# spielekonsole_schaltplan_03_05.net
KiCad netlist of a schematic drawn in EAGLE
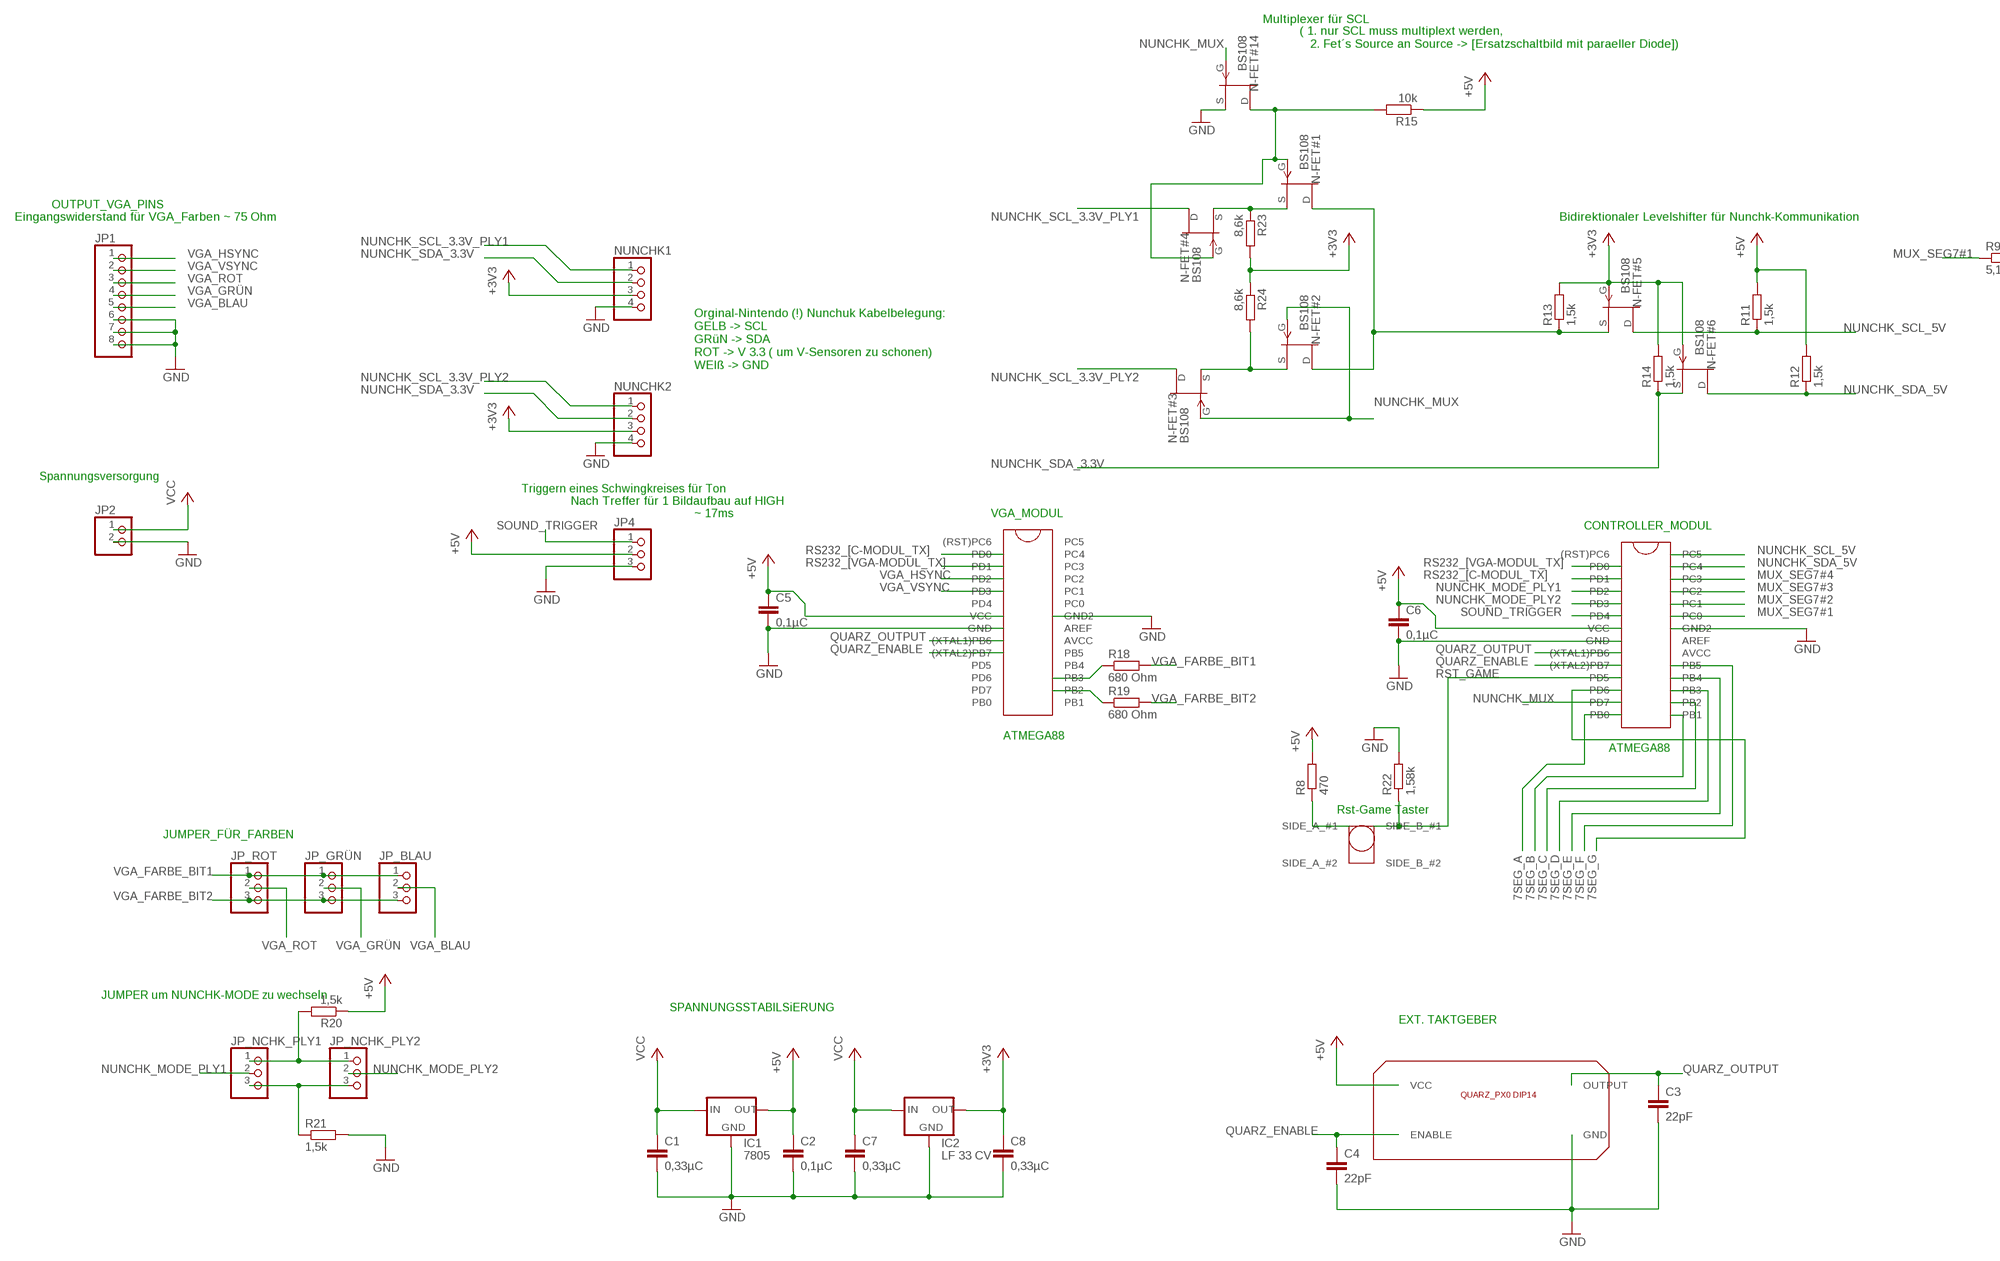
[diagram p0: schematic, sheet 1, part 1 of 2]
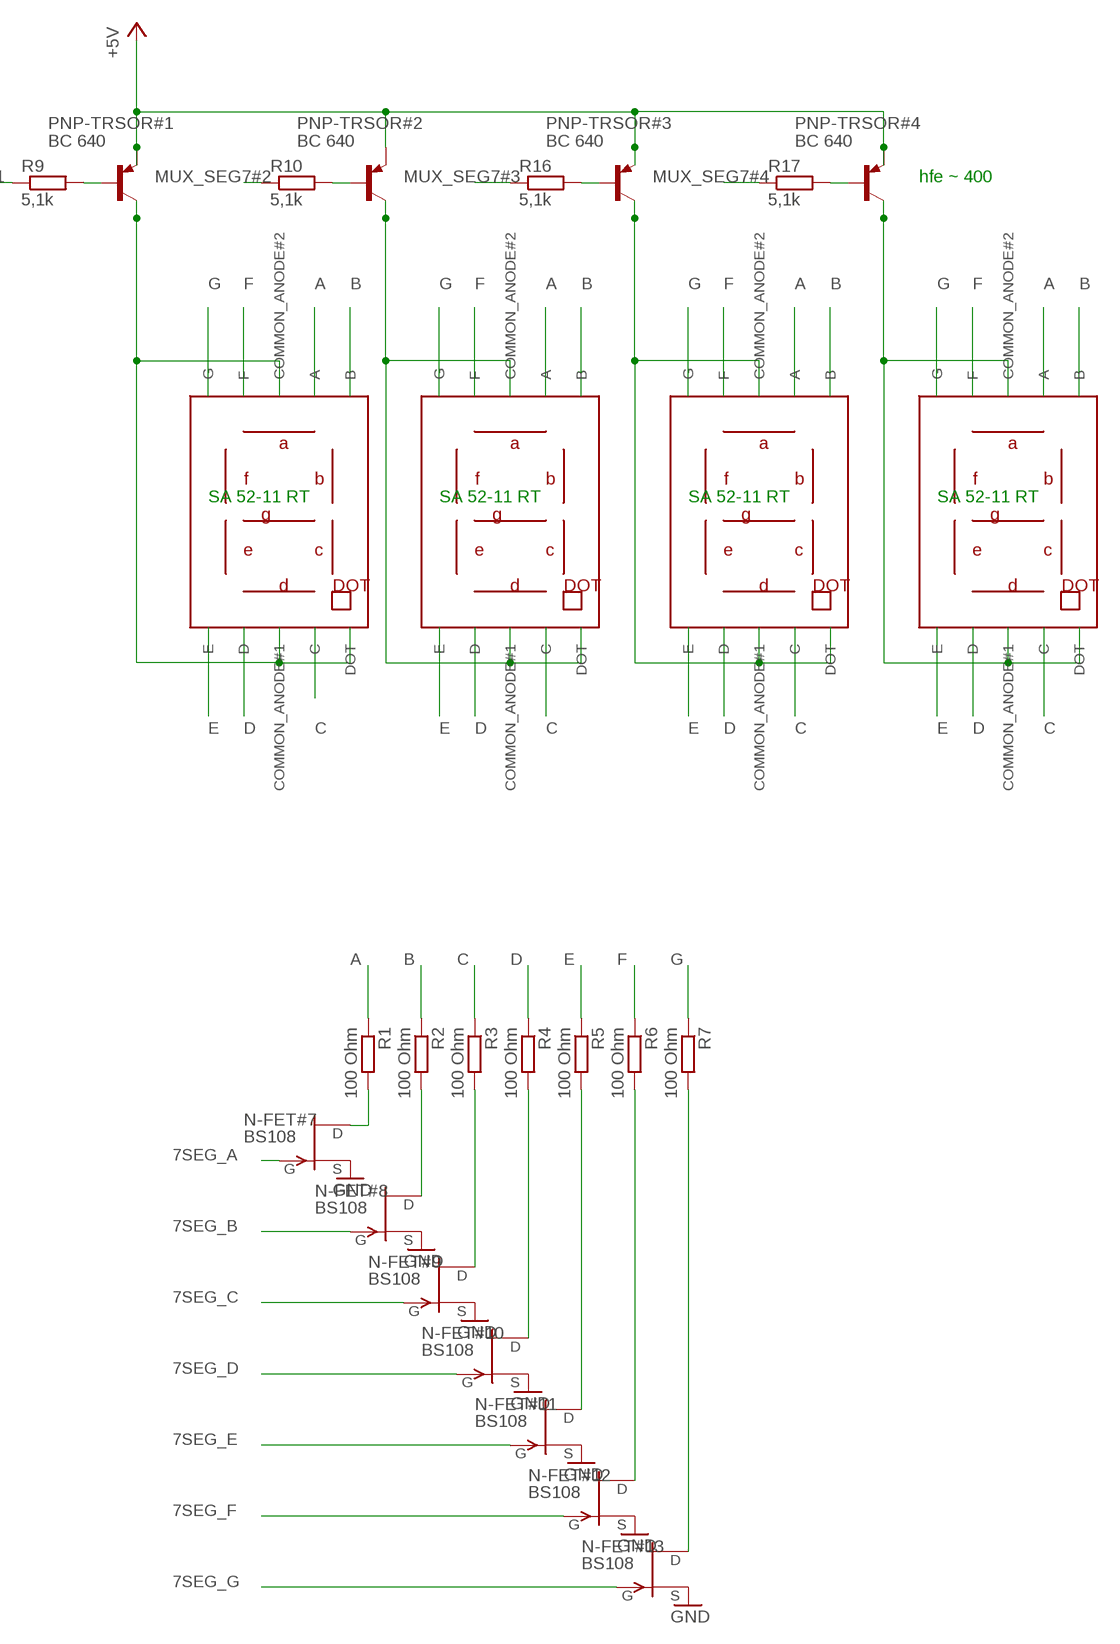
[diagram p1: schematic, sheet 1, part 2 of 2]

(export (version "E")
  (design (tool "Eeschema 10.0.6"))
  (components
    (comp (ref "C1")
      (value "0,33µC")
      (footprint "eagle-import:C025-024X044")
      (libsource (lib "eagle-import") (part "C-EU025-024X044"))
    )
    (comp (ref "C2")
      (value "0,1µC")
      (footprint "eagle-import:C025-024X044")
      (libsource (lib "eagle-import") (part "C-EU025-024X044"))
    )
    (comp (ref "C3")
      (value "22pF")
      (footprint "eagle-import:C025-024X044")
      (libsource (lib "eagle-import") (part "C-EU025-024X044"))
    )
    (comp (ref "C4")
      (value "22pF")
      (footprint "eagle-import:C025-024X044")
      (libsource (lib "eagle-import") (part "C-EU025-024X044"))
    )
    (comp (ref "C5")
      (value "0,1µC")
      (footprint "eagle-import:C025-024X044")
      (libsource (lib "eagle-import") (part "C-EU025-024X044"))
    )
    (comp (ref "C6")
      (value "0,1µC")
      (footprint "eagle-import:C025-024X044")
      (libsource (lib "eagle-import") (part "C-EU025-024X044"))
    )
    (comp (ref "C7")
      (value "0,33µC")
      (footprint "eagle-import:C025-024X044")
      (libsource (lib "eagle-import") (part "C-EU025-024X044"))
    )
    (comp (ref "C8")
      (value "0,33µC")
      (footprint "eagle-import:C025-024X044")
      (libsource (lib "eagle-import") (part "C-EU025-024X044"))
    )
    (comp (ref "IC1")
      (value "7805")
      (footprint "eagle-import:78XXL")
      (libsource (lib "eagle-import") (part "78XXL"))
    )
    (comp (ref "IC2")
      (value "LF 33 CV")
      (footprint "eagle-import:78XXL")
      (libsource (lib "eagle-import") (part "78XXL"))
    )
    (comp (ref "JP1")
      (value "PINHD-1X8")
      (footprint "eagle-import:1X08")
      (libsource (lib "eagle-import") (part "PINHD-1X8"))
    )
    (comp (ref "JP2")
      (value "PINHD-1X2")
      (footprint "eagle-import:1X02")
      (libsource (lib "eagle-import") (part "PINHD-1X2"))
    )
    (comp (ref "JP4")
      (value "PINHD-1X3")
      (footprint "eagle-import:1X03")
      (libsource (lib "eagle-import") (part "PINHD-1X3"))
    )
    (comp (ref "JP_BLAU")
      (value "PINHD-1X3")
      (footprint "eagle-import:1X03")
      (libsource (lib "eagle-import") (part "PINHD-1X3"))
    )
    (comp (ref "JP_GRÜN")
      (value "PINHD-1X3")
      (footprint "eagle-import:1X03")
      (libsource (lib "eagle-import") (part "PINHD-1X3"))
    )
    (comp (ref "JP_NCHK_PLY1")
      (value "PINHD-1X3")
      (footprint "eagle-import:1X03")
      (libsource (lib "eagle-import") (part "PINHD-1X3"))
    )
    (comp (ref "JP_NCHK_PLY2")
      (value "PINHD-1X3")
      (footprint "eagle-import:1X03")
      (libsource (lib "eagle-import") (part "PINHD-1X3"))
    )
    (comp (ref "JP_ROT")
      (value "PINHD-1X3")
      (footprint "eagle-import:1X03")
      (libsource (lib "eagle-import") (part "PINHD-1X3"))
    )
    (comp (ref "N-FET#1")
      (value "BS108")
      (footprint "eagle-import:TO92")
      (libsource (lib "eagle-import") (part "2N3819"))
    )
    (comp (ref "N-FET#2")
      (value "BS108")
      (footprint "eagle-import:TO92")
      (libsource (lib "eagle-import") (part "2N3819"))
    )
    (comp (ref "N-FET#3")
      (value "BS108")
      (footprint "eagle-import:TO92")
      (libsource (lib "eagle-import") (part "2N3819"))
    )
    (comp (ref "N-FET#4")
      (value "BS108")
      (footprint "eagle-import:TO92")
      (libsource (lib "eagle-import") (part "2N3819"))
    )
    (comp (ref "N-FET#5")
      (value "BS108")
      (footprint "eagle-import:TO92")
      (libsource (lib "eagle-import") (part "2N3819"))
    )
    (comp (ref "N-FET#6")
      (value "BS108")
      (footprint "eagle-import:TO92")
      (libsource (lib "eagle-import") (part "2N3819"))
    )
    (comp (ref "N-FET#7")
      (value "BS108")
      (footprint "eagle-import:TO92")
      (libsource (lib "eagle-import") (part "2N3819"))
    )
    (comp (ref "N-FET#8")
      (value "BS108")
      (footprint "eagle-import:TO92")
      (libsource (lib "eagle-import") (part "2N3819"))
    )
    (comp (ref "N-FET#9")
      (value "BS108")
      (footprint "eagle-import:TO92")
      (libsource (lib "eagle-import") (part "2N3819"))
    )
    (comp (ref "N-FET#10")
      (value "BS108")
      (footprint "eagle-import:TO92")
      (libsource (lib "eagle-import") (part "2N3819"))
    )
    (comp (ref "N-FET#11")
      (value "BS108")
      (footprint "eagle-import:TO92")
      (libsource (lib "eagle-import") (part "2N3819"))
    )
    (comp (ref "N-FET#12")
      (value "BS108")
      (footprint "eagle-import:TO92")
      (libsource (lib "eagle-import") (part "2N3819"))
    )
    (comp (ref "N-FET#13")
      (value "BS108")
      (footprint "eagle-import:TO92")
      (libsource (lib "eagle-import") (part "2N3819"))
    )
    (comp (ref "N-FET#14")
      (value "BS108")
      (footprint "eagle-import:TO92")
      (libsource (lib "eagle-import") (part "2N3819"))
    )
    (comp (ref "NUNCHK1")
      (value "PINHD-1X4")
      (footprint "eagle-import:1X04")
      (libsource (lib "eagle-import") (part "PINHD-1X4"))
    )
    (comp (ref "NUNCHK2")
      (value "PINHD-1X4")
      (footprint "eagle-import:1X04")
      (libsource (lib "eagle-import") (part "PINHD-1X4"))
    )
    (comp (ref "PNP-TRSOR#1")
      (value "BC 640")
      (footprint "eagle-import:TO92-CBE")
      (libsource (lib "eagle-import") (part "2N4126"))
    )
    (comp (ref "PNP-TRSOR#2")
      (value "BC 640")
      (footprint "eagle-import:TO92-CBE")
      (libsource (lib "eagle-import") (part "2N4126"))
    )
    (comp (ref "PNP-TRSOR#3")
      (value "BC 640")
      (footprint "eagle-import:TO92-CBE")
      (libsource (lib "eagle-import") (part "2N4126"))
    )
    (comp (ref "PNP-TRSOR#4")
      (value "BC 640")
      (footprint "eagle-import:TO92-CBE")
      (libsource (lib "eagle-import") (part "2N4126"))
    )
    (comp (ref "R1")
      (value "100 Ohm")
      (footprint "eagle-import:0204_7")
      (libsource (lib "eagle-import") (part "R-EU_0204/7"))
    )
    (comp (ref "R2")
      (value "100 Ohm")
      (footprint "eagle-import:0204_7")
      (libsource (lib "eagle-import") (part "R-EU_0204/7"))
    )
    (comp (ref "R3")
      (value "100 Ohm")
      (footprint "eagle-import:0204_7")
      (libsource (lib "eagle-import") (part "R-EU_0204/7"))
    )
    (comp (ref "R4")
      (value "100 Ohm")
      (footprint "eagle-import:0204_7")
      (libsource (lib "eagle-import") (part "R-EU_0204/7"))
    )
    (comp (ref "R5")
      (value "100 Ohm")
      (footprint "eagle-import:0204_7")
      (libsource (lib "eagle-import") (part "R-EU_0204/7"))
    )
    (comp (ref "R6")
      (value "100 Ohm")
      (footprint "eagle-import:0204_7")
      (libsource (lib "eagle-import") (part "R-EU_0204/7"))
    )
    (comp (ref "R7")
      (value "100 Ohm")
      (footprint "eagle-import:0204_7")
      (libsource (lib "eagle-import") (part "R-EU_0204/7"))
    )
    (comp (ref "R8")
      (value "470")
      (footprint "eagle-import:0204_7")
      (libsource (lib "eagle-import") (part "R-EU_0204/7"))
    )
    (comp (ref "R9")
      (value "5,1k")
      (footprint "eagle-import:0204_7")
      (libsource (lib "eagle-import") (part "R-EU_0204/7"))
    )
    (comp (ref "R10")
      (value "5,1k")
      (footprint "eagle-import:0204_7")
      (libsource (lib "eagle-import") (part "R-EU_0204/7"))
    )
    (comp (ref "R11")
      (value "1,5k")
      (footprint "eagle-import:0204_7")
      (libsource (lib "eagle-import") (part "R-EU_0204/7"))
    )
    (comp (ref "R12")
      (value "1,5k")
      (footprint "eagle-import:0204_7")
      (libsource (lib "eagle-import") (part "R-EU_0204/7"))
    )
    (comp (ref "R13")
      (value "1,5k")
      (footprint "eagle-import:0204_7")
      (libsource (lib "eagle-import") (part "R-EU_0204/7"))
    )
    (comp (ref "R14")
      (value "1,5k")
      (footprint "eagle-import:0204_7")
      (libsource (lib "eagle-import") (part "R-EU_0204/7"))
    )
    (comp (ref "R15")
      (value "10k")
      (footprint "eagle-import:0204_7")
      (libsource (lib "eagle-import") (part "R-EU_0204/7"))
    )
    (comp (ref "R16")
      (value "5,1k")
      (footprint "eagle-import:0204_7")
      (libsource (lib "eagle-import") (part "R-EU_0204/7"))
    )
    (comp (ref "R17")
      (value "5,1k")
      (footprint "eagle-import:0204_7")
      (libsource (lib "eagle-import") (part "R-EU_0204/7"))
    )
    (comp (ref "R18")
      (value "680 Ohm")
      (footprint "eagle-import:0204_7")
      (libsource (lib "eagle-import") (part "R-EU_0204/7"))
    )
    (comp (ref "R19")
      (value "680 Ohm")
      (footprint "eagle-import:0204_7")
      (libsource (lib "eagle-import") (part "R-EU_0204/7"))
    )
    (comp (ref "R20")
      (value "1,5k")
      (footprint "eagle-import:0204_7")
      (libsource (lib "eagle-import") (part "R-EU_0204/7"))
    )
    (comp (ref "R21")
      (value "1,5k")
      (footprint "eagle-import:0204_7")
      (libsource (lib "eagle-import") (part "R-EU_0204/7"))
    )
    (comp (ref "R22")
      (value "1,58k")
      (footprint "eagle-import:0204_7")
      (libsource (lib "eagle-import") (part "R-EU_0204/7"))
    )
    (comp (ref "R23")
      (value "8,6k")
      (footprint "eagle-import:0204_7")
      (libsource (lib "eagle-import") (part "R-EU_0204/7"))
    )
    (comp (ref "R24")
      (value "8,6k")
      (footprint "eagle-import:0204_7")
      (libsource (lib "eagle-import") (part "R-EU_0204/7"))
    )
    (comp (ref "U$1")
      (value "ATMEGA 88-20 PU")
      (footprint "eagle-import:ATMEGA8_PAC")
      (libsource (lib "eagle-import") (part "ATMEGA8"))
    )
    (comp (ref "U$2")
      (value "ATMEGA 88-20 PU")
      (footprint "eagle-import:ATMEGA8_PAC")
      (libsource (lib "eagle-import") (part "ATMEGA8"))
    )
    (comp (ref "U$3")
      (value "QUARZ_PX0_DIP14")
      (footprint "eagle-import:QUARZ_PX0_DIP14_PAC")
      (libsource (lib "eagle-import") (part "QUARZ_PX0_DIP14"))
    )
    (comp (ref "U$4")
      (value "SA 52-11 RT")
      (footprint "eagle-import:SIEBEN_SEG_SA52-11_PAC")
      (libsource (lib "eagle-import") (part "SIEBEN_SEG_SA52-11"))
    )
    (comp (ref "U$5")
      (value "SA 52-11 RT")
      (footprint "eagle-import:SIEBEN_SEG_SA52-11_PAC")
      (libsource (lib "eagle-import") (part "SIEBEN_SEG_SA52-11"))
    )
    (comp (ref "U$6")
      (value "SA 52-11 RT")
      (footprint "eagle-import:SIEBEN_SEG_SA52-11_PAC")
      (libsource (lib "eagle-import") (part "SIEBEN_SEG_SA52-11"))
    )
    (comp (ref "U$7")
      (value "SA 52-11 RT")
      (footprint "eagle-import:SIEBEN_SEG_SA52-11_PAC")
      (libsource (lib "eagle-import") (part "SIEBEN_SEG_SA52-11"))
    )
    (comp (ref "U$8")
      (value "TASTER_1")
      (footprint "eagle-import:TASTER_1_PAC")
      (libsource (lib "eagle-import") (part "TASTER_1"))
    )
  )
  (nets
    (net (code "1") (name "+3V3") (class "Default")
      (node (ref "C8") (pin "1") (pinfunction "1_1") (pintype "passive"))
      (node (ref "IC2") (pin "OUT") (pinfunction "OUT_OUT") (pintype "passive"))
      (node (ref "N-FET#5") (pin "2") (pinfunction "G_2") (pintype "passive"))
      (node (ref "N-FET#6") (pin "2") (pinfunction "G_2") (pintype "passive"))
      (node (ref "NUNCHK1") (pin "3") (pinfunction "3_3") (pintype "passive"))
      (node (ref "NUNCHK2") (pin "3") (pinfunction "3_3") (pintype "passive"))
      (node (ref "R13") (pin "2") (pinfunction "2_2") (pintype "passive"))
      (node (ref "R14") (pin "2") (pinfunction "2_2") (pintype "passive"))
      (node (ref "R23") (pin "2") (pinfunction "2_2") (pintype "passive"))
      (node (ref "R24") (pin "1") (pinfunction "1_1") (pintype "passive"))
    )
    (net (code "2") (name "+5V") (class "Default")
      (node (ref "C2") (pin "1") (pinfunction "1_1") (pintype "passive"))
      (node (ref "C5") (pin "1") (pinfunction "1_1") (pintype "passive"))
      (node (ref "C6") (pin "1") (pinfunction "1_1") (pintype "passive"))
      (node (ref "IC1") (pin "OUT") (pinfunction "OUT_OUT") (pintype "passive"))
      (node (ref "JP4") (pin "2") (pinfunction "2_2") (pintype "passive"))
      (node (ref "PNP-TRSOR#1") (pin "E") (pinfunction "E_E") (pintype "passive"))
      (node (ref "PNP-TRSOR#2") (pin "E") (pinfunction "E_E") (pintype "passive"))
      (node (ref "PNP-TRSOR#3") (pin "E") (pinfunction "E_E") (pintype "passive"))
      (node (ref "PNP-TRSOR#4") (pin "E") (pinfunction "E_E") (pintype "passive"))
      (node (ref "R11") (pin "2") (pinfunction "2_2") (pintype "passive"))
      (node (ref "R12") (pin "2") (pinfunction "2_2") (pintype "passive"))
      (node (ref "R15") (pin "1") (pinfunction "1_1") (pintype "passive"))
      (node (ref "R20") (pin "1") (pinfunction "1_1") (pintype "passive"))
      (node (ref "R8") (pin "2") (pinfunction "2_2") (pintype "passive"))
      (node (ref "U$1") (pin "VCC") (pinfunction "VCC_VCC") (pintype "bidirectional"))
      (node (ref "U$2") (pin "VCC") (pinfunction "VCC_VCC") (pintype "bidirectional"))
      (node (ref "U$3") (pin "VCC") (pinfunction "VCC_VCC") (pintype "bidirectional"))
    )
    (net (code "3") (name "/7SEG_A") (class "Default")
      (node (ref "N-FET#7") (pin "2") (pinfunction "G_2") (pintype "passive"))
      (node (ref "U$2") (pin "PB0") (pinfunction "PB0_PB0") (pintype "bidirectional"))
    )
    (net (code "4") (name "/7SEG_B") (class "Default")
      (node (ref "N-FET#8") (pin "2") (pinfunction "G_2") (pintype "passive"))
      (node (ref "U$2") (pin "PB1") (pinfunction "PB1_PB1") (pintype "bidirectional"))
    )
    (net (code "5") (name "/7SEG_C") (class "Default")
      (node (ref "N-FET#9") (pin "2") (pinfunction "G_2") (pintype "passive"))
      (node (ref "U$2") (pin "PB2") (pinfunction "PB2_PB2") (pintype "bidirectional"))
    )
    (net (code "6") (name "/7SEG_D") (class "Default")
      (node (ref "N-FET#10") (pin "2") (pinfunction "G_2") (pintype "passive"))
      (node (ref "U$2") (pin "PB3") (pinfunction "PB3_PB3") (pintype "bidirectional"))
    )
    (net (code "7") (name "/7SEG_E") (class "Default")
      (node (ref "N-FET#11") (pin "2") (pinfunction "G_2") (pintype "passive"))
      (node (ref "U$2") (pin "PB4") (pinfunction "PB4_PB4") (pintype "bidirectional"))
    )
    (net (code "8") (name "/7SEG_F") (class "Default")
      (node (ref "N-FET#12") (pin "2") (pinfunction "G_2") (pintype "passive"))
      (node (ref "U$2") (pin "PB5") (pinfunction "PB5_PB5") (pintype "bidirectional"))
    )
    (net (code "9") (name "/7SEG_G") (class "Default")
      (node (ref "N-FET#13") (pin "2") (pinfunction "G_2") (pintype "passive"))
      (node (ref "U$2") (pin "PD6") (pinfunction "PD6_PD6") (pintype "bidirectional"))
    )
    (net (code "10") (name "/A") (class "Default")
      (node (ref "R1") (pin "1") (pinfunction "1_1") (pintype "passive"))
      (node (ref "U$4") (pin "A") (pinfunction "A_A") (pintype "bidirectional"))
      (node (ref "U$5") (pin "A") (pinfunction "A_A") (pintype "bidirectional"))
      (node (ref "U$6") (pin "A") (pinfunction "A_A") (pintype "bidirectional"))
      (node (ref "U$7") (pin "A") (pinfunction "A_A") (pintype "bidirectional"))
    )
    (net (code "11") (name "/B") (class "Default")
      (node (ref "R2") (pin "1") (pinfunction "1_1") (pintype "passive"))
      (node (ref "U$4") (pin "B") (pinfunction "B_B") (pintype "bidirectional"))
      (node (ref "U$5") (pin "B") (pinfunction "B_B") (pintype "bidirectional"))
      (node (ref "U$6") (pin "B") (pinfunction "B_B") (pintype "bidirectional"))
      (node (ref "U$7") (pin "B") (pinfunction "B_B") (pintype "bidirectional"))
    )
    (net (code "12") (name "/C") (class "Default")
      (node (ref "R3") (pin "1") (pinfunction "1_1") (pintype "passive"))
      (node (ref "U$4") (pin "C") (pinfunction "C_C") (pintype "bidirectional"))
      (node (ref "U$5") (pin "C") (pinfunction "C_C") (pintype "bidirectional"))
      (node (ref "U$6") (pin "C") (pinfunction "C_C") (pintype "bidirectional"))
      (node (ref "U$7") (pin "C") (pinfunction "C_C") (pintype "bidirectional"))
    )
    (net (code "13") (name "/D") (class "Default")
      (node (ref "R4") (pin "1") (pinfunction "1_1") (pintype "passive"))
      (node (ref "U$4") (pin "D") (pinfunction "D_D") (pintype "bidirectional"))
      (node (ref "U$5") (pin "D") (pinfunction "D_D") (pintype "bidirectional"))
      (node (ref "U$6") (pin "D") (pinfunction "D_D") (pintype "bidirectional"))
      (node (ref "U$7") (pin "D") (pinfunction "D_D") (pintype "bidirectional"))
    )
    (net (code "14") (name "/E") (class "Default")
      (node (ref "R5") (pin "1") (pinfunction "1_1") (pintype "passive"))
      (node (ref "U$4") (pin "E") (pinfunction "E_E") (pintype "bidirectional"))
      (node (ref "U$5") (pin "E") (pinfunction "E_E") (pintype "bidirectional"))
      (node (ref "U$6") (pin "E") (pinfunction "E_E") (pintype "bidirectional"))
      (node (ref "U$7") (pin "E") (pinfunction "E_E") (pintype "bidirectional"))
    )
    (net (code "15") (name "/F") (class "Default")
      (node (ref "R6") (pin "1") (pinfunction "1_1") (pintype "passive"))
      (node (ref "U$4") (pin "F") (pinfunction "F_F") (pintype "bidirectional"))
      (node (ref "U$5") (pin "F") (pinfunction "F_F") (pintype "bidirectional"))
      (node (ref "U$6") (pin "F") (pinfunction "F_F") (pintype "bidirectional"))
      (node (ref "U$7") (pin "F") (pinfunction "F_F") (pintype "bidirectional"))
    )
    (net (code "16") (name "/G") (class "Default")
      (node (ref "R7") (pin "1") (pinfunction "1_1") (pintype "passive"))
      (node (ref "U$4") (pin "G") (pinfunction "G_G") (pintype "bidirectional"))
      (node (ref "U$5") (pin "G") (pinfunction "G_G") (pintype "bidirectional"))
      (node (ref "U$6") (pin "G") (pinfunction "G_G") (pintype "bidirectional"))
      (node (ref "U$7") (pin "G") (pinfunction "G_G") (pintype "bidirectional"))
    )
    (net (code "17") (name "/MUX_SEG7#1") (class "Default")
      (node (ref "R9") (pin "1") (pinfunction "1_1") (pintype "passive"))
      (node (ref "U$2") (pin "PC0") (pinfunction "PC0_PC0") (pintype "bidirectional"))
    )
    (net (code "18") (name "/MUX_SEG7#2") (class "Default")
      (node (ref "R10") (pin "1") (pinfunction "1_1") (pintype "passive"))
      (node (ref "U$2") (pin "PC1") (pinfunction "PC1_PC1") (pintype "bidirectional"))
    )
    (net (code "19") (name "/MUX_SEG7#3") (class "Default")
      (node (ref "R16") (pin "1") (pinfunction "1_1") (pintype "passive"))
      (node (ref "U$2") (pin "PC2") (pinfunction "PC2_PC2") (pintype "bidirectional"))
    )
    (net (code "20") (name "/MUX_SEG7#4") (class "Default")
      (node (ref "R17") (pin "1") (pinfunction "1_1") (pintype "passive"))
      (node (ref "U$2") (pin "PC3") (pinfunction "PC3_PC3") (pintype "bidirectional"))
    )
    (net (code "21") (name "/NUNCHK_MODE_PLY1") (class "Default")
      (node (ref "JP_NCHK_PLY1") (pin "2") (pinfunction "2_2") (pintype "passive"))
      (node (ref "U$2") (pin "PD2") (pinfunction "PD2_PD2") (pintype "bidirectional"))
    )
    (net (code "22") (name "/NUNCHK_MODE_PLY2") (class "Default")
      (node (ref "JP_NCHK_PLY2") (pin "2") (pinfunction "2_2") (pintype "passive"))
      (node (ref "U$2") (pin "PD3") (pinfunction "PD3_PD3") (pintype "bidirectional"))
    )
    (net (code "23") (name "/NUNCHK_MUX") (class "Default")
      (node (ref "N-FET#14") (pin "2") (pinfunction "G_2") (pintype "passive"))
      (node (ref "N-FET#2") (pin "2") (pinfunction "G_2") (pintype "passive"))
      (node (ref "N-FET#3") (pin "2") (pinfunction "G_2") (pintype "passive"))
      (node (ref "U$2") (pin "PD7") (pinfunction "PD7_PD7") (pintype "bidirectional"))
    )
    (net (code "24") (name "/NUNCHK_SCL_3.3V_PLY1") (class "Default")
      (node (ref "N-FET#4") (pin "1") (pinfunction "D_1") (pintype "passive"))
      (node (ref "NUNCHK1") (pin "1") (pinfunction "1_1") (pintype "passive"))
    )
    (net (code "25") (name "/NUNCHK_SCL_3.3V_PLY2") (class "Default")
      (node (ref "N-FET#3") (pin "1") (pinfunction "D_1") (pintype "passive"))
      (node (ref "NUNCHK2") (pin "1") (pinfunction "1_1") (pintype "passive"))
    )
    (net (code "26") (name "/NUNCHK_SCL_5V") (class "Default")
      (node (ref "N-FET#5") (pin "1") (pinfunction "D_1") (pintype "passive"))
      (node (ref "R11") (pin "1") (pinfunction "1_1") (pintype "passive"))
      (node (ref "U$2") (pin "PC5") (pinfunction "PC5_PC5") (pintype "bidirectional"))
    )
    (net (code "27") (name "/NUNCHK_SDA_3.3V") (class "Default")
      (node (ref "N-FET#6") (pin "3") (pinfunction "S_3") (pintype "passive"))
      (node (ref "NUNCHK1") (pin "2") (pinfunction "2_2") (pintype "passive"))
      (node (ref "NUNCHK2") (pin "2") (pinfunction "2_2") (pintype "passive"))
      (node (ref "R14") (pin "1") (pinfunction "1_1") (pintype "passive"))
    )
    (net (code "28") (name "/NUNCHK_SDA_5V") (class "Default")
      (node (ref "N-FET#6") (pin "1") (pinfunction "D_1") (pintype "passive"))
      (node (ref "R12") (pin "1") (pinfunction "1_1") (pintype "passive"))
      (node (ref "U$2") (pin "PC4") (pinfunction "PC4_PC4") (pintype "bidirectional"))
    )
    (net (code "29") (name "/QUARZ_ENABLE") (class "Default")
      (node (ref "C4") (pin "1") (pinfunction "1_1") (pintype "passive"))
      (node (ref "U$1") (pin "PB7") (pinfunction "(XTAL2)PB7_PB7") (pintype "bidirectional"))
      (node (ref "U$2") (pin "PB7") (pinfunction "(XTAL2)PB7_PB7") (pintype "bidirectional"))
      (node (ref "U$3") (pin "ENABLE") (pinfunction "ENABLE_ENABLE") (pintype "bidirectional"))
    )
    (net (code "30") (name "/QUARZ_OUTPUT") (class "Default")
      (node (ref "C3") (pin "1") (pinfunction "1_1") (pintype "passive"))
      (node (ref "U$1") (pin "PB6") (pinfunction "(XTAL1)PB6_PB6") (pintype "bidirectional"))
      (node (ref "U$2") (pin "PB6") (pinfunction "(XTAL1)PB6_PB6") (pintype "bidirectional"))
      (node (ref "U$3") (pin "OUTPUT") (pinfunction "OUTPUT_OUTPUT") (pintype "bidirectional"))
    )
    (net (code "31") (name "/RS232_[C-MODUL_TX]") (class "Default")
      (node (ref "U$1") (pin "PD0") (pinfunction "PD0_PD0") (pintype "bidirectional"))
      (node (ref "U$2") (pin "PD1") (pinfunction "PD1_PD1") (pintype "bidirectional"))
    )
    (net (code "32") (name "/RS232_[VGA-MODUL_TX]") (class "Default")
      (node (ref "U$1") (pin "PD1") (pinfunction "PD1_PD1") (pintype "bidirectional"))
      (node (ref "U$2") (pin "PD0") (pinfunction "PD0_PD0") (pintype "bidirectional"))
    )
    (net (code "33") (name "/RST_GAME") (class "Default")
      (node (ref "R22") (pin "1") (pinfunction "1_1") (pintype "passive"))
      (node (ref "U$2") (pin "PD5") (pinfunction "PD5_PD5") (pintype "bidirectional"))
      (node (ref "U$8") (pin "SIDE_B_#1") (pinfunction "SIDE_B_#1_SIDE_B_#1") (pintype "bidirectional"))
    )
    (net (code "34") (name "/SOUND_TRIGGER") (class "Default")
      (node (ref "JP4") (pin "1") (pinfunction "1_1") (pintype "passive"))
      (node (ref "U$2") (pin "PD4") (pinfunction "PD4_PD4") (pintype "bidirectional"))
    )
    (net (code "35") (name "/VGA_BLAU") (class "Default")
      (node (ref "JP1") (pin "5") (pinfunction "5_5") (pintype "passive"))
      (node (ref "JP_BLAU") (pin "2") (pinfunction "2_2") (pintype "passive"))
    )
    (net (code "36") (name "/VGA_FARBE_BIT1") (class "Default")
      (node (ref "JP_BLAU") (pin "1") (pinfunction "1_1") (pintype "passive"))
      (node (ref "JP_GRÜN") (pin "1") (pinfunction "1_1") (pintype "passive"))
      (node (ref "JP_ROT") (pin "1") (pinfunction "1_1") (pintype "passive"))
      (node (ref "R18") (pin "2") (pinfunction "2_2") (pintype "passive"))
    )
    (net (code "37") (name "/VGA_FARBE_BIT2") (class "Default")
      (node (ref "JP_BLAU") (pin "3") (pinfunction "3_3") (pintype "passive"))
      (node (ref "JP_GRÜN") (pin "3") (pinfunction "3_3") (pintype "passive"))
      (node (ref "JP_ROT") (pin "3") (pinfunction "3_3") (pintype "passive"))
      (node (ref "R19") (pin "2") (pinfunction "2_2") (pintype "passive"))
    )
    (net (code "38") (name "/VGA_GRÜN") (class "Default")
      (node (ref "JP1") (pin "4") (pinfunction "4_4") (pintype "passive"))
      (node (ref "JP_GRÜN") (pin "2") (pinfunction "2_2") (pintype "passive"))
    )
    (net (code "39") (name "/VGA_HSYNC") (class "Default")
      (node (ref "JP1") (pin "1") (pinfunction "1_1") (pintype "passive"))
      (node (ref "U$1") (pin "PD2") (pinfunction "PD2_PD2") (pintype "bidirectional"))
    )
    (net (code "40") (name "/VGA_ROT") (class "Default")
      (node (ref "JP1") (pin "3") (pinfunction "3_3") (pintype "passive"))
      (node (ref "JP_ROT") (pin "2") (pinfunction "2_2") (pintype "passive"))
    )
    (net (code "41") (name "/VGA_VSYNC") (class "Default")
      (node (ref "JP1") (pin "2") (pinfunction "2_2") (pintype "passive"))
      (node (ref "U$1") (pin "PD3") (pinfunction "PD3_PD3") (pintype "bidirectional"))
    )
    (net (code "42") (name "GND") (class "Default")
      (node (ref "C1") (pin "2") (pinfunction "2_2") (pintype "passive"))
      (node (ref "C2") (pin "2") (pinfunction "2_2") (pintype "passive"))
      (node (ref "C3") (pin "2") (pinfunction "2_2") (pintype "passive"))
      (node (ref "C4") (pin "2") (pinfunction "2_2") (pintype "passive"))
      (node (ref "C5") (pin "2") (pinfunction "2_2") (pintype "passive"))
      (node (ref "C6") (pin "2") (pinfunction "2_2") (pintype "passive"))
      (node (ref "C7") (pin "2") (pinfunction "2_2") (pintype "passive"))
      (node (ref "C8") (pin "2") (pinfunction "2_2") (pintype "passive"))
      (node (ref "IC1") (pin "GND") (pinfunction "GND_GND") (pintype "input"))
      (node (ref "IC2") (pin "GND") (pinfunction "GND_GND") (pintype "input"))
      (node (ref "JP1") (pin "6") (pinfunction "6_6") (pintype "passive"))
      (node (ref "JP1") (pin "7") (pinfunction "7_7") (pintype "passive"))
      (node (ref "JP1") (pin "8") (pinfunction "8_8") (pintype "passive"))
      (node (ref "JP2") (pin "2") (pinfunction "2_2") (pintype "passive"))
      (node (ref "JP4") (pin "3") (pinfunction "3_3") (pintype "passive"))
      (node (ref "N-FET#10") (pin "3") (pinfunction "S_3") (pintype "passive"))
      (node (ref "N-FET#11") (pin "3") (pinfunction "S_3") (pintype "passive"))
      (node (ref "N-FET#12") (pin "3") (pinfunction "S_3") (pintype "passive"))
      (node (ref "N-FET#13") (pin "3") (pinfunction "S_3") (pintype "passive"))
      (node (ref "N-FET#14") (pin "3") (pinfunction "S_3") (pintype "passive"))
      (node (ref "N-FET#7") (pin "3") (pinfunction "S_3") (pintype "passive"))
      (node (ref "N-FET#8") (pin "3") (pinfunction "S_3") (pintype "passive"))
      (node (ref "N-FET#9") (pin "3") (pinfunction "S_3") (pintype "passive"))
      (node (ref "NUNCHK1") (pin "4") (pinfunction "4_4") (pintype "passive"))
      (node (ref "NUNCHK2") (pin "4") (pinfunction "4_4") (pintype "passive"))
      (node (ref "R21") (pin "2") (pinfunction "2_2") (pintype "passive"))
      (node (ref "R22") (pin "2") (pinfunction "2_2") (pintype "passive"))
      (node (ref "U$1") (pin "GND1") (pinfunction "GND_GND1") (pintype "bidirectional"))
      (node (ref "U$1") (pin "GND2") (pinfunction "GND2_GND2") (pintype "bidirectional"))
      (node (ref "U$2") (pin "GND1") (pinfunction "GND_GND1") (pintype "bidirectional"))
      (node (ref "U$2") (pin "GND2") (pinfunction "GND2_GND2") (pintype "bidirectional"))
      (node (ref "U$3") (pin "GND") (pinfunction "GND_GND") (pintype "bidirectional"))
    )
    (net (code "43") (name "Net-(JP_NCHK_PLY1-Pad1)") (class "Default")
      (node (ref "JP_NCHK_PLY1") (pin "1") (pinfunction "1_1") (pintype "passive"))
      (node (ref "JP_NCHK_PLY2") (pin "1") (pinfunction "1_1") (pintype "passive"))
      (node (ref "R20") (pin "2") (pinfunction "2_2") (pintype "passive"))
    )
    (net (code "44") (name "Net-(JP_NCHK_PLY1-Pad3)") (class "Default")
      (node (ref "JP_NCHK_PLY1") (pin "3") (pinfunction "3_3") (pintype "passive"))
      (node (ref "JP_NCHK_PLY2") (pin "3") (pinfunction "3_3") (pintype "passive"))
      (node (ref "R21") (pin "1") (pinfunction "1_1") (pintype "passive"))
    )
    (net (code "45") (name "Net-(N-FET#1-D)") (class "Default")
      (node (ref "N-FET#1") (pin "1") (pinfunction "D_1") (pintype "passive"))
      (node (ref "N-FET#2") (pin "1") (pinfunction "D_1") (pintype "passive"))
      (node (ref "N-FET#5") (pin "3") (pinfunction "S_3") (pintype "passive"))
      (node (ref "R13") (pin "1") (pinfunction "1_1") (pintype "passive"))
    )
    (net (code "46") (name "Net-(N-FET#1-G)") (class "Default")
      (node (ref "N-FET#1") (pin "2") (pinfunction "G_2") (pintype "passive"))
      (node (ref "N-FET#14") (pin "1") (pinfunction "D_1") (pintype "passive"))
      (node (ref "N-FET#4") (pin "2") (pinfunction "G_2") (pintype "passive"))
      (node (ref "R15") (pin "2") (pinfunction "2_2") (pintype "passive"))
    )
    (net (code "47") (name "Net-(N-FET#1-S)") (class "Default")
      (node (ref "N-FET#1") (pin "3") (pinfunction "S_3") (pintype "passive"))
      (node (ref "N-FET#4") (pin "3") (pinfunction "S_3") (pintype "passive"))
      (node (ref "R23") (pin "1") (pinfunction "1_1") (pintype "passive"))
    )
    (net (code "48") (name "Net-(N-FET#2-S)") (class "Default")
      (node (ref "N-FET#2") (pin "3") (pinfunction "S_3") (pintype "passive"))
      (node (ref "N-FET#3") (pin "3") (pinfunction "S_3") (pintype "passive"))
      (node (ref "R24") (pin "2") (pinfunction "2_2") (pintype "passive"))
    )
    (net (code "49") (name "Net-(N-FET#7-D)") (class "Default")
      (node (ref "N-FET#7") (pin "1") (pinfunction "D_1") (pintype "passive"))
      (node (ref "R1") (pin "2") (pinfunction "2_2") (pintype "passive"))
    )
    (net (code "50") (name "Net-(N-FET#8-D)") (class "Default")
      (node (ref "N-FET#8") (pin "1") (pinfunction "D_1") (pintype "passive"))
      (node (ref "R2") (pin "2") (pinfunction "2_2") (pintype "passive"))
    )
    (net (code "51") (name "Net-(N-FET#9-D)") (class "Default")
      (node (ref "N-FET#9") (pin "1") (pinfunction "D_1") (pintype "passive"))
      (node (ref "R3") (pin "2") (pinfunction "2_2") (pintype "passive"))
    )
    (net (code "52") (name "Net-(N-FET#10-D)") (class "Default")
      (node (ref "N-FET#10") (pin "1") (pinfunction "D_1") (pintype "passive"))
      (node (ref "R4") (pin "2") (pinfunction "2_2") (pintype "passive"))
    )
    (net (code "53") (name "Net-(N-FET#11-D)") (class "Default")
      (node (ref "N-FET#11") (pin "1") (pinfunction "D_1") (pintype "passive"))
      (node (ref "R5") (pin "2") (pinfunction "2_2") (pintype "passive"))
    )
    (net (code "54") (name "Net-(N-FET#12-D)") (class "Default")
      (node (ref "N-FET#12") (pin "1") (pinfunction "D_1") (pintype "passive"))
      (node (ref "R6") (pin "2") (pinfunction "2_2") (pintype "passive"))
    )
    (net (code "55") (name "Net-(N-FET#13-D)") (class "Default")
      (node (ref "N-FET#13") (pin "1") (pinfunction "D_1") (pintype "passive"))
      (node (ref "R7") (pin "2") (pinfunction "2_2") (pintype "passive"))
    )
    (net (code "56") (name "Net-(PNP-TRSOR#1-PadB)") (class "Default")
      (node (ref "PNP-TRSOR#1") (pin "B") (pinfunction "B_B") (pintype "passive"))
      (node (ref "R9") (pin "2") (pinfunction "2_2") (pintype "passive"))
    )
    (net (code "57") (name "Net-(PNP-TRSOR#1-PadC)") (class "Default")
      (node (ref "PNP-TRSOR#1") (pin "C") (pinfunction "C_C") (pintype "passive"))
      (node (ref "U$4") (pin "COMMON_ANODE#1") (pinfunction "COMMON_ANODE#1_COMMON_ANODE#1") (pintype "bidirectional"))
      (node (ref "U$4") (pin "COMMON_ANODE#2") (pinfunction "COMMON_ANODE#2_COMMON_ANODE#2") (pintype "bidirectional"))
      (node (ref "U$4") (pin "DOT") (pinfunction "DOT_DOT") (pintype "bidirectional"))
    )
    (net (code "58") (name "Net-(PNP-TRSOR#2-PadB)") (class "Default")
      (node (ref "PNP-TRSOR#2") (pin "B") (pinfunction "B_B") (pintype "passive"))
      (node (ref "R10") (pin "2") (pinfunction "2_2") (pintype "passive"))
    )
    (net (code "59") (name "Net-(PNP-TRSOR#2-PadC)") (class "Default")
      (node (ref "PNP-TRSOR#2") (pin "C") (pinfunction "C_C") (pintype "passive"))
      (node (ref "U$5") (pin "COMMON_ANODE#1") (pinfunction "COMMON_ANODE#1_COMMON_ANODE#1") (pintype "bidirectional"))
      (node (ref "U$5") (pin "COMMON_ANODE#2") (pinfunction "COMMON_ANODE#2_COMMON_ANODE#2") (pintype "bidirectional"))
      (node (ref "U$5") (pin "DOT") (pinfunction "DOT_DOT") (pintype "bidirectional"))
    )
    (net (code "60") (name "Net-(PNP-TRSOR#3-PadB)") (class "Default")
      (node (ref "PNP-TRSOR#3") (pin "B") (pinfunction "B_B") (pintype "passive"))
      (node (ref "R16") (pin "2") (pinfunction "2_2") (pintype "passive"))
    )
    (net (code "61") (name "Net-(PNP-TRSOR#3-PadC)") (class "Default")
      (node (ref "PNP-TRSOR#3") (pin "C") (pinfunction "C_C") (pintype "passive"))
      (node (ref "U$6") (pin "COMMON_ANODE#1") (pinfunction "COMMON_ANODE#1_COMMON_ANODE#1") (pintype "bidirectional"))
      (node (ref "U$6") (pin "COMMON_ANODE#2") (pinfunction "COMMON_ANODE#2_COMMON_ANODE#2") (pintype "bidirectional"))
      (node (ref "U$6") (pin "DOT") (pinfunction "DOT_DOT") (pintype "bidirectional"))
    )
    (net (code "62") (name "Net-(PNP-TRSOR#4-PadB)") (class "Default")
      (node (ref "PNP-TRSOR#4") (pin "B") (pinfunction "B_B") (pintype "passive"))
      (node (ref "R17") (pin "2") (pinfunction "2_2") (pintype "passive"))
    )
    (net (code "63") (name "Net-(PNP-TRSOR#4-PadC)") (class "Default")
      (node (ref "PNP-TRSOR#4") (pin "C") (pinfunction "C_C") (pintype "passive"))
      (node (ref "U$7") (pin "COMMON_ANODE#1") (pinfunction "COMMON_ANODE#1_COMMON_ANODE#1") (pintype "bidirectional"))
      (node (ref "U$7") (pin "COMMON_ANODE#2") (pinfunction "COMMON_ANODE#2_COMMON_ANODE#2") (pintype "bidirectional"))
      (node (ref "U$7") (pin "DOT") (pinfunction "DOT_DOT") (pintype "bidirectional"))
    )
    (net (code "64") (name "Net-(R8-Pad1)") (class "Default")
      (node (ref "R8") (pin "1") (pinfunction "1_1") (pintype "passive"))
      (node (ref "U$8") (pin "SIDE_A_#1") (pinfunction "SIDE_A_#1_SIDE_A_#1") (pintype "bidirectional"))
    )
    (net (code "65") (name "Net-(R18-Pad1)") (class "Default")
      (node (ref "R18") (pin "1") (pinfunction "1_1") (pintype "passive"))
      (node (ref "U$1") (pin "PB3") (pinfunction "PB3_PB3") (pintype "bidirectional"))
    )
    (net (code "66") (name "Net-(R19-Pad1)") (class "Default")
      (node (ref "R19") (pin "1") (pinfunction "1_1") (pintype "passive"))
      (node (ref "U$1") (pin "PB2") (pinfunction "PB2_PB2") (pintype "bidirectional"))
    )
    (net (code "67") (name "VCC") (class "Default")
      (node (ref "C1") (pin "1") (pinfunction "1_1") (pintype "passive"))
      (node (ref "C7") (pin "1") (pinfunction "1_1") (pintype "passive"))
      (node (ref "IC1") (pin "IN") (pinfunction "IN_IN") (pintype "input"))
      (node (ref "IC2") (pin "IN") (pinfunction "IN_IN") (pintype "input"))
      (node (ref "JP2") (pin "1") (pinfunction "1_1") (pintype "passive"))
    )
    (net (code "68") (name "unconnected-(U$1-(RST)PC6-PadPC6)") (class "Default")
      (node (ref "U$1") (pin "PC6") (pinfunction "(RST)PC6_PC6") (pintype "bidirectional"))
    )
    (net (code "69") (name "unconnected-(U$1-PadAREF)") (class "Default")
      (node (ref "U$1") (pin "AREF") (pinfunction "AREF_AREF") (pintype "bidirectional"))
    )
    (net (code "70") (name "unconnected-(U$1-PadAVCC)") (class "Default")
      (node (ref "U$1") (pin "AVCC") (pinfunction "AVCC_AVCC") (pintype "bidirectional"))
    )
    (net (code "71") (name "unconnected-(U$1-PadPB0)") (class "Default")
      (node (ref "U$1") (pin "PB0") (pinfunction "PB0_PB0") (pintype "bidirectional"))
    )
    (net (code "72") (name "unconnected-(U$1-PadPB1)") (class "Default")
      (node (ref "U$1") (pin "PB1") (pinfunction "PB1_PB1") (pintype "bidirectional"))
    )
    (net (code "73") (name "unconnected-(U$1-PadPB4)") (class "Default")
      (node (ref "U$1") (pin "PB4") (pinfunction "PB4_PB4") (pintype "bidirectional"))
    )
    (net (code "74") (name "unconnected-(U$1-PadPB5)") (class "Default")
      (node (ref "U$1") (pin "PB5") (pinfunction "PB5_PB5") (pintype "bidirectional"))
    )
    (net (code "75") (name "unconnected-(U$1-PadPC0)") (class "Default")
      (node (ref "U$1") (pin "PC0") (pinfunction "PC0_PC0") (pintype "bidirectional"))
    )
    (net (code "76") (name "unconnected-(U$1-PadPC1)") (class "Default")
      (node (ref "U$1") (pin "PC1") (pinfunction "PC1_PC1") (pintype "bidirectional"))
    )
    (net (code "77") (name "unconnected-(U$1-PadPC2)") (class "Default")
      (node (ref "U$1") (pin "PC2") (pinfunction "PC2_PC2") (pintype "bidirectional"))
    )
    (net (code "78") (name "unconnected-(U$1-PadPC3)") (class "Default")
      (node (ref "U$1") (pin "PC3") (pinfunction "PC3_PC3") (pintype "bidirectional"))
    )
    (net (code "79") (name "unconnected-(U$1-PadPC4)") (class "Default")
      (node (ref "U$1") (pin "PC4") (pinfunction "PC4_PC4") (pintype "bidirectional"))
    )
    (net (code "80") (name "unconnected-(U$1-PadPC5)") (class "Default")
      (node (ref "U$1") (pin "PC5") (pinfunction "PC5_PC5") (pintype "bidirectional"))
    )
    (net (code "81") (name "unconnected-(U$1-PadPD4)") (class "Default")
      (node (ref "U$1") (pin "PD4") (pinfunction "PD4_PD4") (pintype "bidirectional"))
    )
    (net (code "82") (name "unconnected-(U$1-PadPD5)") (class "Default")
      (node (ref "U$1") (pin "PD5") (pinfunction "PD5_PD5") (pintype "bidirectional"))
    )
    (net (code "83") (name "unconnected-(U$1-PadPD6)") (class "Default")
      (node (ref "U$1") (pin "PD6") (pinfunction "PD6_PD6") (pintype "bidirectional"))
    )
    (net (code "84") (name "unconnected-(U$1-PadPD7)") (class "Default")
      (node (ref "U$1") (pin "PD7") (pinfunction "PD7_PD7") (pintype "bidirectional"))
    )
    (net (code "85") (name "unconnected-(U$2-(RST)PC6-PadPC6)") (class "Default")
      (node (ref "U$2") (pin "PC6") (pinfunction "(RST)PC6_PC6") (pintype "bidirectional"))
    )
    (net (code "86") (name "unconnected-(U$2-PadAREF)") (class "Default")
      (node (ref "U$2") (pin "AREF") (pinfunction "AREF_AREF") (pintype "bidirectional"))
    )
    (net (code "87") (name "unconnected-(U$2-PadAVCC)") (class "Default")
      (node (ref "U$2") (pin "AVCC") (pinfunction "AVCC_AVCC") (pintype "bidirectional"))
    )
    (net (code "88") (name "unconnected-(U$8-PadSIDE_A_#2)") (class "Default")
      (node (ref "U$8") (pin "SIDE_A_#2") (pinfunction "SIDE_A_#2_SIDE_A_#2") (pintype "bidirectional"))
    )
    (net (code "89") (name "unconnected-(U$8-PadSIDE_B_#2)") (class "Default")
      (node (ref "U$8") (pin "SIDE_B_#2") (pinfunction "SIDE_B_#2_SIDE_B_#2") (pintype "bidirectional"))
    )
  )
)
